# P_RAM_aux.net
KiCad netlist of a schematic drawn in Altium Designer
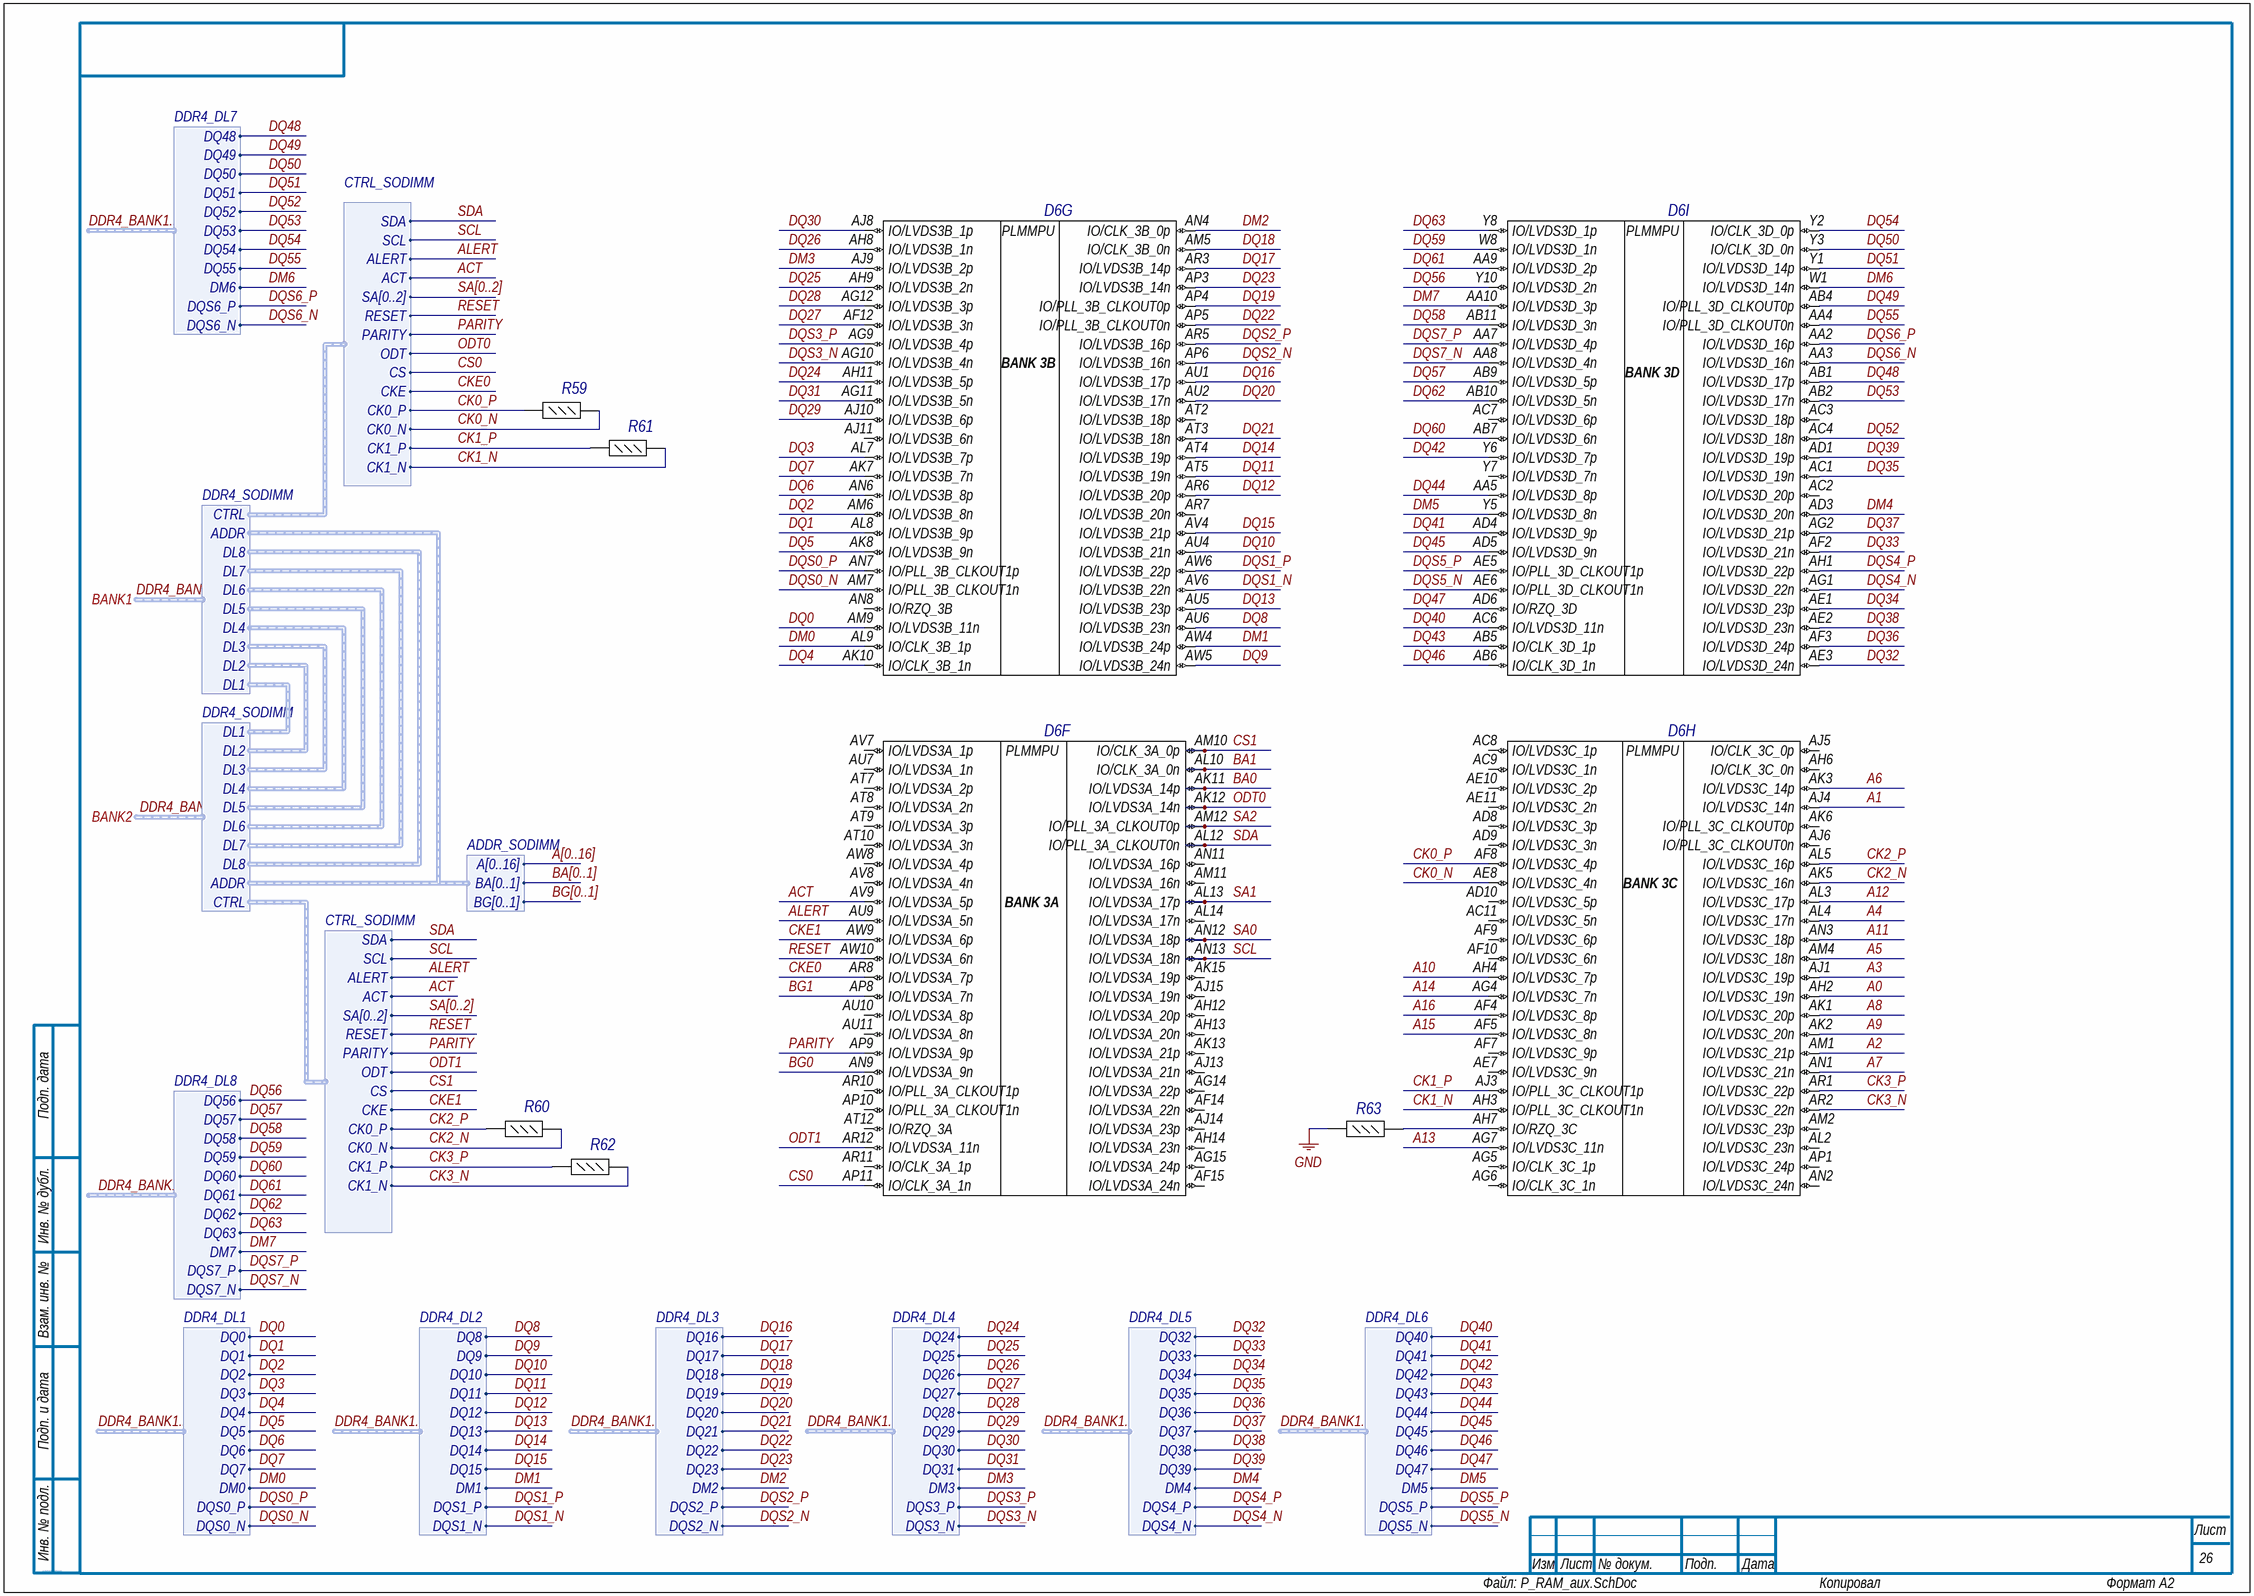
[diagram p0: P_RAM_aux.SchDoc]

(export (version "E")
  (design (tool "Eeschema 10.0.6"))
  (components
    (comp (ref "D6")
      (value "10AS066N3F40E2SGE2")
      (footprint "ALTR-FBGA1517_A-350")
      (libsource (lib "MiniPC DB") (part "10AS066N3F40"))
    )
    (comp (ref "R59")
      (value "RC0402JR-0739RL")
      (footprint "RESC1005X40X25LL05T05")
      (description "Chip Resistor, 39 Ohm, +/- 5%, 0.063 W, -55 to 155 degC, 0402 (1005 Metric), RoHS, Tape and Reel")
      (fields (field (name "TOLERANCE") "5%"))
      (libsource (lib "MiniPC DB") (part "RES-0.05"))
    )
    (comp (ref "R60")
      (value "RC0402JR-0739RL")
      (footprint "RESC1005X40X25LL05T05")
      (description "Chip Resistor, 39 Ohm, +/- 5%, 0.063 W, -55 to 155 degC, 0402 (1005 Metric), RoHS, Tape and Reel")
      (fields (field (name "TOLERANCE") "5%"))
      (libsource (lib "MiniPC DB") (part "RES-0.05"))
    )
    (comp (ref "R61")
      (value "RC0402JR-0739RL")
      (footprint "RESC1005X40X25LL05T05")
      (description "Chip Resistor, 39 Ohm, +/- 5%, 0.063 W, -55 to 155 degC, 0402 (1005 Metric), RoHS, Tape and Reel")
      (fields (field (name "TOLERANCE") "5%"))
      (libsource (lib "MiniPC DB") (part "RES-0.05"))
    )
    (comp (ref "R62")
      (value "RC0402JR-0739RL")
      (footprint "RESC1005X40X25LL05T05")
      (description "Chip Resistor, 39 Ohm, +/- 5%, 0.063 W, -55 to 155 degC, 0402 (1005 Metric), RoHS, Tape and Reel")
      (fields (field (name "TOLERANCE") "5%"))
      (libsource (lib "MiniPC DB") (part "RES-0.05"))
    )
    (comp (ref "R63")
      (value "RC0402JR-0739RL")
      (footprint "RESC1005X40X25LL05T05")
      (description "Chip Resistor, 39 Ohm, +/- 5%, 0.063 W, -55 to 155 degC, 0402 (1005 Metric), RoHS, Tape and Reel")
      (fields (field (name "TOLERANCE") "5%"))
      (libsource (lib "MiniPC DB") (part "RES-0.05"))
    )
  )
  (nets
    (net (code "14") (name "/A0") (class "Default")
      (node (ref "D6") (pin "AH2") (pinfunction "IO/LVDS3C_19n_AH2") (pintype "bidirectional"))
    )
    (net (code "15") (name "/A1") (class "Default")
      (node (ref "D6") (pin "AJ4") (pinfunction "IO/LVDS3C_14n_AJ4") (pintype "bidirectional"))
    )
    (net (code "16") (name "/A2") (class "Default")
      (node (ref "D6") (pin "AM1") (pinfunction "IO/LVDS3C_21p_AM1") (pintype "bidirectional"))
    )
    (net (code "17") (name "/A3") (class "Default")
      (node (ref "D6") (pin "AJ1") (pinfunction "IO/LVDS3C_19p_AJ1") (pintype "bidirectional"))
    )
    (net (code "18") (name "/A4") (class "Default")
      (node (ref "D6") (pin "AL4") (pinfunction "IO/LVDS3C_17n_AL4") (pintype "bidirectional"))
    )
    (net (code "19") (name "/A5") (class "Default")
      (node (ref "D6") (pin "AM4") (pinfunction "IO/LVDS3C_18n_AM4") (pintype "bidirectional"))
    )
    (net (code "20") (name "/A6") (class "Default")
      (node (ref "D6") (pin "AK3") (pinfunction "IO/LVDS3C_14p_AK3") (pintype "bidirectional"))
    )
    (net (code "21") (name "/A7") (class "Default")
      (node (ref "D6") (pin "AN1") (pinfunction "IO/LVDS3C_21n_AN1") (pintype "bidirectional"))
    )
    (net (code "22") (name "/A8") (class "Default")
      (node (ref "D6") (pin "AK1") (pinfunction "IO/LVDS3C_20p_AK1") (pintype "bidirectional"))
    )
    (net (code "23") (name "/A9") (class "Default")
      (node (ref "D6") (pin "AK2") (pinfunction "IO/LVDS3C_20n_AK2") (pintype "bidirectional"))
    )
    (net (code "24") (name "/A10") (class "Default")
      (node (ref "D6") (pin "AH4") (pinfunction "IO/LVDS3C_7p_AH4") (pintype "bidirectional"))
    )
    (net (code "25") (name "/A11") (class "Default")
      (node (ref "D6") (pin "AN3") (pinfunction "IO/LVDS3C_18p_AN3") (pintype "bidirectional"))
    )
    (net (code "26") (name "/A12") (class "Default")
      (node (ref "D6") (pin "AL3") (pinfunction "IO/LVDS3C_17p_AL3") (pintype "bidirectional"))
    )
    (net (code "27") (name "/A13") (class "Default")
      (node (ref "D6") (pin "AG7") (pinfunction "IO/LVDS3C_11n_AG7") (pintype "bidirectional"))
    )
    (net (code "28") (name "/A14") (class "Default")
      (node (ref "D6") (pin "AG4") (pinfunction "IO/LVDS3C_7n_AG4") (pintype "bidirectional"))
    )
    (net (code "29") (name "/A15") (class "Default")
      (node (ref "D6") (pin "AF5") (pinfunction "IO/LVDS3C_8n_AF5") (pintype "bidirectional"))
    )
    (net (code "30") (name "/A16") (class "Default")
      (node (ref "D6") (pin "AF4") (pinfunction "IO/LVDS3C_8p_AF4") (pintype "bidirectional"))
    )
    (net (code "31") (name "/ACT") (class "Default")
      (node (ref "D6") (pin "AV9") (pinfunction "IO/LVDS3A_5p_AV9") (pintype "bidirectional"))
    )
    (net (code "32") (name "/ALERT") (class "Default")
      (node (ref "D6") (pin "AU9") (pinfunction "IO/LVDS3A_5n_AU9") (pintype "bidirectional"))
    )
    (net (code "34") (name "/BA0") (class "Default")
      (node (ref "D6") (pin "AK11") (pinfunction "IO/LVDS3A_14p_AK11") (pintype "bidirectional"))
    )
    (net (code "35") (name "/BA1") (class "Default")
      (node (ref "D6") (pin "AL10") (pinfunction "IO/CLK_3A_0n_AL10") (pintype "bidirectional"))
    )
    (net (code "37") (name "/BG0") (class "Default")
      (node (ref "D6") (pin "AN9") (pinfunction "IO/LVDS3A_9n_AN9") (pintype "bidirectional"))
    )
    (net (code "38") (name "/BG1") (class "Default")
      (node (ref "D6") (pin "AP8") (pinfunction "IO/LVDS3A_7n_AP8") (pintype "bidirectional"))
    )
    (net (code "40") (name "/CK0_N") (class "Default")
      (node (ref "D6") (pin "AE8") (pinfunction "IO/LVDS3C_4n_AE8") (pintype "bidirectional"))
      (node (ref "R59") (pin "2") (pinfunction "2_2") (pintype "passive"))
    )
    (net (code "41") (name "/CK0_P") (class "Default")
      (node (ref "D6") (pin "AF8") (pinfunction "IO/LVDS3C_4p_AF8") (pintype "bidirectional"))
      (node (ref "R59") (pin "1") (pinfunction "1_1") (pintype "passive"))
    )
    (net (code "42") (name "/CK1_N") (class "Default")
      (node (ref "D6") (pin "AH3") (pinfunction "IO/PLL_3C_CLKOUT1n_AH3") (pintype "bidirectional"))
      (node (ref "R61") (pin "2") (pinfunction "2_2") (pintype "passive"))
    )
    (net (code "43") (name "/CK1_P") (class "Default")
      (node (ref "D6") (pin "AJ3") (pinfunction "IO/PLL_3C_CLKOUT1p_AJ3") (pintype "bidirectional"))
      (node (ref "R61") (pin "1") (pinfunction "1_1") (pintype "passive"))
    )
    (net (code "44") (name "/CK2_N") (class "Default")
      (node (ref "D6") (pin "AK5") (pinfunction "IO/LVDS3C_16n_AK5") (pintype "bidirectional"))
      (node (ref "R60") (pin "2") (pinfunction "2_2") (pintype "passive"))
    )
    (net (code "45") (name "/CK2_P") (class "Default")
      (node (ref "D6") (pin "AL5") (pinfunction "IO/LVDS3C_16p_AL5") (pintype "bidirectional"))
      (node (ref "R60") (pin "1") (pinfunction "1_1") (pintype "passive"))
    )
    (net (code "46") (name "/CK3_N") (class "Default")
      (node (ref "D6") (pin "AR2") (pinfunction "IO/LVDS3C_22n_AR2") (pintype "bidirectional"))
      (node (ref "R62") (pin "2") (pinfunction "2_2") (pintype "passive"))
    )
    (net (code "47") (name "/CK3_P") (class "Default")
      (node (ref "D6") (pin "AR1") (pinfunction "IO/LVDS3C_22p_AR1") (pintype "bidirectional"))
      (node (ref "R62") (pin "1") (pinfunction "1_1") (pintype "passive"))
    )
    (net (code "48") (name "/CKE0") (class "Default")
      (node (ref "D6") (pin "AR8") (pinfunction "IO/LVDS3A_7p_AR8") (pintype "bidirectional"))
    )
    (net (code "49") (name "/CKE1") (class "Default")
      (node (ref "D6") (pin "AW9") (pinfunction "IO/LVDS3A_6p_AW9") (pintype "bidirectional"))
    )
    (net (code "50") (name "/CS0") (class "Default")
      (node (ref "D6") (pin "AP11") (pinfunction "IO/CLK_3A_1n_AP11") (pintype "bidirectional"))
    )
    (net (code "51") (name "/CS1") (class "Default")
      (node (ref "D6") (pin "AM10") (pinfunction "IO/CLK_3A_0p_AM10") (pintype "bidirectional"))
    )
    (net (code "60") (name "/DM0") (class "Default")
      (node (ref "D6") (pin "AL9") (pinfunction "IO/CLK_3B_1p_AL9") (pintype "bidirectional"))
    )
    (net (code "61") (name "/DM1") (class "Default")
      (node (ref "D6") (pin "AW4") (pinfunction "IO/LVDS3B_24p_AW4") (pintype "bidirectional"))
    )
    (net (code "62") (name "/DM2") (class "Default")
      (node (ref "D6") (pin "AN4") (pinfunction "IO/CLK_3B_0p_AN4") (pintype "bidirectional"))
    )
    (net (code "63") (name "/DM3") (class "Default")
      (node (ref "D6") (pin "AJ9") (pinfunction "IO/LVDS3B_2p_AJ9") (pintype "bidirectional"))
    )
    (net (code "64") (name "/DM4") (class "Default")
      (node (ref "D6") (pin "AD3") (pinfunction "IO/LVDS3D_20n_AD3") (pintype "bidirectional"))
    )
    (net (code "65") (name "/DM5") (class "Default")
      (node (ref "D6") (pin "Y5") (pinfunction "IO/LVDS3D_8n_Y5") (pintype "bidirectional"))
    )
    (net (code "66") (name "/DM6") (class "Default")
      (node (ref "D6") (pin "W1") (pinfunction "IO/LVDS3D_14n_W1") (pintype "bidirectional"))
    )
    (net (code "67") (name "/DM7") (class "Default")
      (node (ref "D6") (pin "AA10") (pinfunction "IO/LVDS3D_3p_AA10") (pintype "bidirectional"))
    )
    (net (code "68") (name "/DQ0") (class "Default")
      (node (ref "D6") (pin "AM9") (pinfunction "IO/LVDS3B_11n_AM9") (pintype "bidirectional"))
    )
    (net (code "69") (name "/DQ1") (class "Default")
      (node (ref "D6") (pin "AL8") (pinfunction "IO/LVDS3B_9p_AL8") (pintype "bidirectional"))
    )
    (net (code "70") (name "/DQ2") (class "Default")
      (node (ref "D6") (pin "AM6") (pinfunction "IO/LVDS3B_8n_AM6") (pintype "bidirectional"))
    )
    (net (code "71") (name "/DQ3") (class "Default")
      (node (ref "D6") (pin "AL7") (pinfunction "IO/LVDS3B_7p_AL7") (pintype "bidirectional"))
    )
    (net (code "72") (name "/DQ4") (class "Default")
      (node (ref "D6") (pin "AK10") (pinfunction "IO/CLK_3B_1n_AK10") (pintype "bidirectional"))
    )
    (net (code "73") (name "/DQ5") (class "Default")
      (node (ref "D6") (pin "AK8") (pinfunction "IO/LVDS3B_9n_AK8") (pintype "bidirectional"))
    )
    (net (code "74") (name "/DQ6") (class "Default")
      (node (ref "D6") (pin "AN6") (pinfunction "IO/LVDS3B_8p_AN6") (pintype "bidirectional"))
    )
    (net (code "75") (name "/DQ7") (class "Default")
      (node (ref "D6") (pin "AK7") (pinfunction "IO/LVDS3B_7n_AK7") (pintype "bidirectional"))
    )
    (net (code "76") (name "/DQ8") (class "Default")
      (node (ref "D6") (pin "AU6") (pinfunction "IO/LVDS3B_23n_AU6") (pintype "bidirectional"))
    )
    (net (code "77") (name "/DQ9") (class "Default")
      (node (ref "D6") (pin "AW5") (pinfunction "IO/LVDS3B_24n_AW5") (pintype "bidirectional"))
    )
    (net (code "78") (name "/DQ10") (class "Default")
      (node (ref "D6") (pin "AU4") (pinfunction "IO/LVDS3B_21n_AU4") (pintype "bidirectional"))
    )
    (net (code "79") (name "/DQ11") (class "Default")
      (node (ref "D6") (pin "AT5") (pinfunction "IO/LVDS3B_19n_AT5") (pintype "bidirectional"))
    )
    (net (code "80") (name "/DQ12") (class "Default")
      (node (ref "D6") (pin "AR6") (pinfunction "IO/LVDS3B_20p_AR6") (pintype "bidirectional"))
    )
    (net (code "81") (name "/DQ13") (class "Default")
      (node (ref "D6") (pin "AU5") (pinfunction "IO/LVDS3B_23p_AU5") (pintype "bidirectional"))
    )
    (net (code "82") (name "/DQ14") (class "Default")
      (node (ref "D6") (pin "AT4") (pinfunction "IO/LVDS3B_19p_AT4") (pintype "bidirectional"))
    )
    (net (code "83") (name "/DQ15") (class "Default")
      (node (ref "D6") (pin "AV4") (pinfunction "IO/LVDS3B_21p_AV4") (pintype "bidirectional"))
    )
    (net (code "84") (name "/DQ16") (class "Default")
      (node (ref "D6") (pin "AU1") (pinfunction "IO/LVDS3B_17p_AU1") (pintype "bidirectional"))
    )
    (net (code "85") (name "/DQ17") (class "Default")
      (node (ref "D6") (pin "AR3") (pinfunction "IO/LVDS3B_14p_AR3") (pintype "bidirectional"))
    )
    (net (code "86") (name "/DQ18") (class "Default")
      (node (ref "D6") (pin "AM5") (pinfunction "IO/CLK_3B_0n_AM5") (pintype "bidirectional"))
    )
    (net (code "87") (name "/DQ19") (class "Default")
      (node (ref "D6") (pin "AP4") (pinfunction "IO/PLL_3B_CLKOUT0p_AP4") (pintype "bidirectional"))
    )
    (net (code "88") (name "/DQ20") (class "Default")
      (node (ref "D6") (pin "AU2") (pinfunction "IO/LVDS3B_17n_AU2") (pintype "bidirectional"))
    )
    (net (code "89") (name "/DQ21") (class "Default")
      (node (ref "D6") (pin "AT3") (pinfunction "IO/LVDS3B_18n_AT3") (pintype "bidirectional"))
    )
    (net (code "90") (name "/DQ22") (class "Default")
      (node (ref "D6") (pin "AP5") (pinfunction "IO/PLL_3B_CLKOUT0n_AP5") (pintype "bidirectional"))
    )
    (net (code "91") (name "/DQ23") (class "Default")
      (node (ref "D6") (pin "AP3") (pinfunction "IO/LVDS3B_14n_AP3") (pintype "bidirectional"))
    )
    (net (code "92") (name "/DQ24") (class "Default")
      (node (ref "D6") (pin "AH11") (pinfunction "IO/LVDS3B_5p_AH11") (pintype "bidirectional"))
    )
    (net (code "93") (name "/DQ25") (class "Default")
      (node (ref "D6") (pin "AH9") (pinfunction "IO/LVDS3B_2n_AH9") (pintype "bidirectional"))
    )
    (net (code "94") (name "/DQ26") (class "Default")
      (node (ref "D6") (pin "AH8") (pinfunction "IO/LVDS3B_1n_AH8") (pintype "bidirectional"))
    )
    (net (code "95") (name "/DQ27") (class "Default")
      (node (ref "D6") (pin "AF12") (pinfunction "IO/LVDS3B_3n_AF12") (pintype "bidirectional"))
    )
    (net (code "96") (name "/DQ28") (class "Default")
      (node (ref "D6") (pin "AG12") (pinfunction "IO/LVDS3B_3p_AG12") (pintype "bidirectional"))
    )
    (net (code "97") (name "/DQ29") (class "Default")
      (node (ref "D6") (pin "AJ10") (pinfunction "IO/LVDS3B_6p_AJ10") (pintype "bidirectional"))
    )
    (net (code "98") (name "/DQ30") (class "Default")
      (node (ref "D6") (pin "AJ8") (pinfunction "IO/LVDS3B_1p_AJ8") (pintype "bidirectional"))
    )
    (net (code "99") (name "/DQ31") (class "Default")
      (node (ref "D6") (pin "AG11") (pinfunction "IO/LVDS3B_5n_AG11") (pintype "bidirectional"))
    )
    (net (code "100") (name "/DQ32") (class "Default")
      (node (ref "D6") (pin "AE3") (pinfunction "IO/LVDS3D_24n_AE3") (pintype "bidirectional"))
    )
    (net (code "101") (name "/DQ33") (class "Default")
      (node (ref "D6") (pin "AF2") (pinfunction "IO/LVDS3D_21n_AF2") (pintype "bidirectional"))
    )
    (net (code "102") (name "/DQ34") (class "Default")
      (node (ref "D6") (pin "AE1") (pinfunction "IO/LVDS3D_23p_AE1") (pintype "bidirectional"))
    )
    (net (code "103") (name "/DQ35") (class "Default")
      (node (ref "D6") (pin "AC1") (pinfunction "IO/LVDS3D_19n_AC1") (pintype "bidirectional"))
    )
    (net (code "104") (name "/DQ36") (class "Default")
      (node (ref "D6") (pin "AF3") (pinfunction "IO/LVDS3D_24p_AF3") (pintype "bidirectional"))
    )
    (net (code "105") (name "/DQ37") (class "Default")
      (node (ref "D6") (pin "AG2") (pinfunction "IO/LVDS3D_21p_AG2") (pintype "bidirectional"))
    )
    (net (code "106") (name "/DQ38") (class "Default")
      (node (ref "D6") (pin "AE2") (pinfunction "IO/LVDS3D_23n_AE2") (pintype "bidirectional"))
    )
    (net (code "107") (name "/DQ39") (class "Default")
      (node (ref "D6") (pin "AD1") (pinfunction "IO/LVDS3D_19p_AD1") (pintype "bidirectional"))
    )
    (net (code "108") (name "/DQ40") (class "Default")
      (node (ref "D6") (pin "AC6") (pinfunction "IO/LVDS3D_11n_AC6") (pintype "bidirectional"))
    )
    (net (code "109") (name "/DQ41") (class "Default")
      (node (ref "D6") (pin "AD4") (pinfunction "IO/LVDS3D_9p_AD4") (pintype "bidirectional"))
    )
    (net (code "110") (name "/DQ42") (class "Default")
      (node (ref "D6") (pin "Y6") (pinfunction "IO/LVDS3D_7p_Y6") (pintype "bidirectional"))
    )
    (net (code "111") (name "/DQ43") (class "Default")
      (node (ref "D6") (pin "AB5") (pinfunction "IO/CLK_3D_1p_AB5") (pintype "bidirectional"))
    )
    (net (code "112") (name "/DQ44") (class "Default")
      (node (ref "D6") (pin "AA5") (pinfunction "IO/LVDS3D_8p_AA5") (pintype "bidirectional"))
    )
    (net (code "113") (name "/DQ45") (class "Default")
      (node (ref "D6") (pin "AD5") (pinfunction "IO/LVDS3D_9n_AD5") (pintype "bidirectional"))
    )
    (net (code "114") (name "/DQ46") (class "Default")
      (node (ref "D6") (pin "AB6") (pinfunction "IO/CLK_3D_1n_AB6") (pintype "bidirectional"))
    )
    (net (code "115") (name "/DQ47") (class "Default")
      (node (ref "D6") (pin "AD6") (pinfunction "IO/RZQ_3D_AD6") (pintype "bidirectional"))
    )
    (net (code "116") (name "/DQ48") (class "Default")
      (node (ref "D6") (pin "AB1") (pinfunction "IO/LVDS3D_17p_AB1") (pintype "bidirectional"))
    )
    (net (code "117") (name "/DQ49") (class "Default")
      (node (ref "D6") (pin "AB4") (pinfunction "IO/PLL_3D_CLKOUT0p_AB4") (pintype "bidirectional"))
    )
    (net (code "118") (name "/DQ50") (class "Default")
      (node (ref "D6") (pin "Y3") (pinfunction "IO/CLK_3D_0n_Y3") (pintype "bidirectional"))
    )
    (net (code "119") (name "/DQ51") (class "Default")
      (node (ref "D6") (pin "Y1") (pinfunction "IO/LVDS3D_14p_Y1") (pintype "bidirectional"))
    )
    (net (code "120") (name "/DQ52") (class "Default")
      (node (ref "D6") (pin "AC4") (pinfunction "IO/LVDS3D_18n_AC4") (pintype "bidirectional"))
    )
    (net (code "121") (name "/DQ53") (class "Default")
      (node (ref "D6") (pin "AB2") (pinfunction "IO/LVDS3D_17n_AB2") (pintype "bidirectional"))
    )
    (net (code "122") (name "/DQ54") (class "Default")
      (node (ref "D6") (pin "Y2") (pinfunction "IO/CLK_3D_0p_Y2") (pintype "bidirectional"))
    )
    (net (code "123") (name "/DQ55") (class "Default")
      (node (ref "D6") (pin "AA4") (pinfunction "IO/PLL_3D_CLKOUT0n_AA4") (pintype "bidirectional"))
    )
    (net (code "124") (name "/DQ56") (class "Default")
      (node (ref "D6") (pin "Y10") (pinfunction "IO/LVDS3D_2n_Y10") (pintype "bidirectional"))
    )
    (net (code "125") (name "/DQ57") (class "Default")
      (node (ref "D6") (pin "AB9") (pinfunction "IO/LVDS3D_5p_AB9") (pintype "bidirectional"))
    )
    (net (code "126") (name "/DQ58") (class "Default")
      (node (ref "D6") (pin "AB11") (pinfunction "IO/LVDS3D_3n_AB11") (pintype "bidirectional"))
    )
    (net (code "127") (name "/DQ59") (class "Default")
      (node (ref "D6") (pin "W8") (pinfunction "IO/LVDS3D_1n_W8") (pintype "bidirectional"))
    )
    (net (code "128") (name "/DQ60") (class "Default")
      (node (ref "D6") (pin "AB7") (pinfunction "IO/LVDS3D_6n_AB7") (pintype "bidirectional"))
    )
    (net (code "129") (name "/DQ61") (class "Default")
      (node (ref "D6") (pin "AA9") (pinfunction "IO/LVDS3D_2p_AA9") (pintype "bidirectional"))
    )
    (net (code "130") (name "/DQ62") (class "Default")
      (node (ref "D6") (pin "AB10") (pinfunction "IO/LVDS3D_5n_AB10") (pintype "bidirectional"))
    )
    (net (code "131") (name "/DQ63") (class "Default")
      (node (ref "D6") (pin "Y8") (pinfunction "IO/LVDS3D_1p_Y8") (pintype "bidirectional"))
    )
    (net (code "132") (name "/DQS0_N") (class "Default")
      (node (ref "D6") (pin "AM7") (pinfunction "IO/PLL_3B_CLKOUT1n_AM7") (pintype "bidirectional"))
    )
    (net (code "133") (name "/DQS0_P") (class "Default")
      (node (ref "D6") (pin "AN7") (pinfunction "IO/PLL_3B_CLKOUT1p_AN7") (pintype "bidirectional"))
    )
    (net (code "134") (name "/DQS1_N") (class "Default")
      (node (ref "D6") (pin "AV6") (pinfunction "IO/LVDS3B_22n_AV6") (pintype "bidirectional"))
    )
    (net (code "135") (name "/DQS1_P") (class "Default")
      (node (ref "D6") (pin "AW6") (pinfunction "IO/LVDS3B_22p_AW6") (pintype "bidirectional"))
    )
    (net (code "136") (name "/DQS2_N") (class "Default")
      (node (ref "D6") (pin "AP6") (pinfunction "IO/LVDS3B_16n_AP6") (pintype "bidirectional"))
    )
    (net (code "137") (name "/DQS2_P") (class "Default")
      (node (ref "D6") (pin "AR5") (pinfunction "IO/LVDS3B_16p_AR5") (pintype "bidirectional"))
    )
    (net (code "138") (name "/DQS3_N") (class "Default")
      (node (ref "D6") (pin "AG10") (pinfunction "IO/LVDS3B_4n_AG10") (pintype "bidirectional"))
    )
    (net (code "139") (name "/DQS3_P") (class "Default")
      (node (ref "D6") (pin "AG9") (pinfunction "IO/LVDS3B_4p_AG9") (pintype "bidirectional"))
    )
    (net (code "140") (name "/DQS4_N") (class "Default")
      (node (ref "D6") (pin "AG1") (pinfunction "IO/LVDS3D_22n_AG1") (pintype "bidirectional"))
    )
    (net (code "141") (name "/DQS4_P") (class "Default")
      (node (ref "D6") (pin "AH1") (pinfunction "IO/LVDS3D_22p_AH1") (pintype "bidirectional"))
    )
    (net (code "142") (name "/DQS5_N") (class "Default")
      (node (ref "D6") (pin "AE6") (pinfunction "IO/PLL_3D_CLKOUT1n_AE6") (pintype "bidirectional"))
    )
    (net (code "143") (name "/DQS5_P") (class "Default")
      (node (ref "D6") (pin "AE5") (pinfunction "IO/PLL_3D_CLKOUT1p_AE5") (pintype "bidirectional"))
    )
    (net (code "144") (name "/DQS6_N") (class "Default")
      (node (ref "D6") (pin "AA3") (pinfunction "IO/LVDS3D_16n_AA3") (pintype "bidirectional"))
    )
    (net (code "145") (name "/DQS6_P") (class "Default")
      (node (ref "D6") (pin "AA2") (pinfunction "IO/LVDS3D_16p_AA2") (pintype "bidirectional"))
    )
    (net (code "146") (name "/DQS7_N") (class "Default")
      (node (ref "D6") (pin "AA8") (pinfunction "IO/LVDS3D_4n_AA8") (pintype "bidirectional"))
    )
    (net (code "147") (name "/DQS7_P") (class "Default")
      (node (ref "D6") (pin "AA7") (pinfunction "IO/LVDS3D_4p_AA7") (pintype "bidirectional"))
    )
    (net (code "148") (name "/ODT0") (class "Default")
      (node (ref "D6") (pin "AK12") (pinfunction "IO/LVDS3A_14n_AK12") (pintype "bidirectional"))
    )
    (net (code "149") (name "/ODT1") (class "Default")
      (node (ref "D6") (pin "AR12") (pinfunction "IO/LVDS3A_11n_AR12") (pintype "bidirectional"))
    )
    (net (code "150") (name "/PARITY") (class "Default")
      (node (ref "D6") (pin "AP9") (pinfunction "IO/LVDS3A_9p_AP9") (pintype "bidirectional"))
    )
    (net (code "151") (name "/RESET") (class "Default")
      (node (ref "D6") (pin "AW10") (pinfunction "IO/LVDS3A_6n_AW10") (pintype "bidirectional"))
    )
    (net (code "152") (name "/SA0") (class "Default")
      (node (ref "D6") (pin "AN12") (pinfunction "IO/LVDS3A_18p_AN12") (pintype "bidirectional"))
    )
    (net (code "153") (name "/SA1") (class "Default")
      (node (ref "D6") (pin "AL13") (pinfunction "IO/LVDS3A_17p_AL13") (pintype "bidirectional"))
    )
    (net (code "154") (name "/SA2") (class "Default")
      (node (ref "D6") (pin "AM12") (pinfunction "IO/PLL_3A_CLKOUT0p_AM12") (pintype "bidirectional"))
    )
    (net (code "156") (name "/SCL") (class "Default")
      (node (ref "D6") (pin "AN13") (pinfunction "IO/LVDS3A_18n_AN13") (pintype "bidirectional"))
    )
    (net (code "157") (name "/SDA") (class "Default")
      (node (ref "D6") (pin "AL12") (pinfunction "IO/PLL_3A_CLKOUT0n_AL12") (pintype "bidirectional"))
    )
    (net (code "164") (name "GND") (class "Default")
      (node (ref "R63") (pin "1") (pinfunction "1_1") (pintype "passive"))
    )
    (net (code "165") (name "Net-(D6H-IO{slash}RZQ_3C)") (class "Default")
      (node (ref "D6") (pin "AH7") (pinfunction "IO/RZQ_3C_AH7") (pintype "bidirectional"))
      (node (ref "R63") (pin "2") (pinfunction "2_2") (pintype "passive"))
    )
    (net (code "166") (name "unconnected-(D6F-IO{slash}CLK_3A_1p-PadAR11)") (class "Default")
      (node (ref "D6") (pin "AR11") (pinfunction "IO/CLK_3A_1p_AR11") (pintype "bidirectional"))
    )
    (net (code "167") (name "unconnected-(D6F-IO{slash}LVDS3A_1n-PadAU7)") (class "Default")
      (node (ref "D6") (pin "AU7") (pinfunction "IO/LVDS3A_1n_AU7") (pintype "bidirectional"))
    )
    (net (code "168") (name "unconnected-(D6F-IO{slash}LVDS3A_1p-PadAV7)") (class "Default")
      (node (ref "D6") (pin "AV7") (pinfunction "IO/LVDS3A_1p_AV7") (pintype "bidirectional"))
    )
    (net (code "169") (name "unconnected-(D6F-IO{slash}LVDS3A_2n-PadAT8)") (class "Default")
      (node (ref "D6") (pin "AT8") (pinfunction "IO/LVDS3A_2n_AT8") (pintype "bidirectional"))
    )
    (net (code "170") (name "unconnected-(D6F-IO{slash}LVDS3A_2p-PadAT7)") (class "Default")
      (node (ref "D6") (pin "AT7") (pinfunction "IO/LVDS3A_2p_AT7") (pintype "bidirectional"))
    )
    (net (code "171") (name "unconnected-(D6F-IO{slash}LVDS3A_3n-PadAT10)") (class "Default")
      (node (ref "D6") (pin "AT10") (pinfunction "IO/LVDS3A_3n_AT10") (pintype "bidirectional"))
    )
    (net (code "172") (name "unconnected-(D6F-IO{slash}LVDS3A_3p-PadAT9)") (class "Default")
      (node (ref "D6") (pin "AT9") (pinfunction "IO/LVDS3A_3p_AT9") (pintype "bidirectional"))
    )
    (net (code "173") (name "unconnected-(D6F-IO{slash}LVDS3A_4n-PadAV8)") (class "Default")
      (node (ref "D6") (pin "AV8") (pinfunction "IO/LVDS3A_4n_AV8") (pintype "bidirectional"))
    )
    (net (code "174") (name "unconnected-(D6F-IO{slash}LVDS3A_4p-PadAW8)") (class "Default")
      (node (ref "D6") (pin "AW8") (pinfunction "IO/LVDS3A_4p_AW8") (pintype "bidirectional"))
    )
    (net (code "175") (name "unconnected-(D6F-IO{slash}LVDS3A_8n-PadAU11)") (class "Default")
      (node (ref "D6") (pin "AU11") (pinfunction "IO/LVDS3A_8n_AU11") (pintype "bidirectional"))
    )
    (net (code "176") (name "unconnected-(D6F-IO{slash}LVDS3A_8p-PadAU10)") (class "Default")
      (node (ref "D6") (pin "AU10") (pinfunction "IO/LVDS3A_8p_AU10") (pintype "bidirectional"))
    )
    (net (code "177") (name "unconnected-(D6F-IO{slash}LVDS3A_16n-PadAM11)") (class "Default")
      (node (ref "D6") (pin "AM11") (pinfunction "IO/LVDS3A_16n_AM11") (pintype "bidirectional"))
    )
    (net (code "178") (name "unconnected-(D6F-IO{slash}LVDS3A_16p-PadAN11)") (class "Default")
      (node (ref "D6") (pin "AN11") (pinfunction "IO/LVDS3A_16p_AN11") (pintype "bidirectional"))
    )
    (net (code "179") (name "unconnected-(D6F-IO{slash}LVDS3A_17n-PadAL14)") (class "Default")
      (node (ref "D6") (pin "AL14") (pinfunction "IO/LVDS3A_17n_AL14") (pintype "bidirectional"))
    )
    (net (code "180") (name "unconnected-(D6F-IO{slash}LVDS3A_19n-PadAJ15)") (class "Default")
      (node (ref "D6") (pin "AJ15") (pinfunction "IO/LVDS3A_19n_AJ15") (pintype "bidirectional"))
    )
    (net (code "181") (name "unconnected-(D6F-IO{slash}LVDS3A_19p-PadAK15)") (class "Default")
      (node (ref "D6") (pin "AK15") (pinfunction "IO/LVDS3A_19p_AK15") (pintype "bidirectional"))
    )
    (net (code "182") (name "unconnected-(D6F-IO{slash}LVDS3A_20n-PadAH13)") (class "Default")
      (node (ref "D6") (pin "AH13") (pinfunction "IO/LVDS3A_20n_AH13") (pintype "bidirectional"))
    )
    (net (code "183") (name "unconnected-(D6F-IO{slash}LVDS3A_20p-PadAH12)") (class "Default")
      (node (ref "D6") (pin "AH12") (pinfunction "IO/LVDS3A_20p_AH12") (pintype "bidirectional"))
    )
    (net (code "184") (name "unconnected-(D6F-IO{slash}LVDS3A_21n-PadAJ13)") (class "Default")
      (node (ref "D6") (pin "AJ13") (pinfunction "IO/LVDS3A_21n_AJ13") (pintype "bidirectional"))
    )
    (net (code "185") (name "unconnected-(D6F-IO{slash}LVDS3A_21p-PadAK13)") (class "Default")
      (node (ref "D6") (pin "AK13") (pinfunction "IO/LVDS3A_21p_AK13") (pintype "bidirectional"))
    )
    (net (code "186") (name "unconnected-(D6F-IO{slash}LVDS3A_22n-PadAF14)") (class "Default")
      (node (ref "D6") (pin "AF14") (pinfunction "IO/LVDS3A_22n_AF14") (pintype "bidirectional"))
    )
    (net (code "187") (name "unconnected-(D6F-IO{slash}LVDS3A_22p-PadAG14)") (class "Default")
      (node (ref "D6") (pin "AG14") (pinfunction "IO/LVDS3A_22p_AG14") (pintype "bidirectional"))
    )
    (net (code "188") (name "unconnected-(D6F-IO{slash}LVDS3A_23n-PadAH14)") (class "Default")
      (node (ref "D6") (pin "AH14") (pinfunction "IO/LVDS3A_23n_AH14") (pintype "bidirectional"))
    )
    (net (code "189") (name "unconnected-(D6F-IO{slash}LVDS3A_23p-PadAJ14)") (class "Default")
      (node (ref "D6") (pin "AJ14") (pinfunction "IO/LVDS3A_23p_AJ14") (pintype "bidirectional"))
    )
    (net (code "190") (name "unconnected-(D6F-IO{slash}LVDS3A_24n-PadAF15)") (class "Default")
      (node (ref "D6") (pin "AF15") (pinfunction "IO/LVDS3A_24n_AF15") (pintype "bidirectional"))
    )
    (net (code "191") (name "unconnected-(D6F-IO{slash}LVDS3A_24p-PadAG15)") (class "Default")
      (node (ref "D6") (pin "AG15") (pinfunction "IO/LVDS3A_24p_AG15") (pintype "bidirectional"))
    )
    (net (code "192") (name "unconnected-(D6F-IO{slash}PLL_3A_CLKOUT1n-PadAP10)") (class "Default")
      (node (ref "D6") (pin "AP10") (pinfunction "IO/PLL_3A_CLKOUT1n_AP10") (pintype "bidirectional"))
    )
    (net (code "193") (name "unconnected-(D6F-IO{slash}PLL_3A_CLKOUT1p-PadAR10)") (class "Default")
      (node (ref "D6") (pin "AR10") (pinfunction "IO/PLL_3A_CLKOUT1p_AR10") (pintype "bidirectional"))
    )
    (net (code "194") (name "unconnected-(D6F-IO{slash}RZQ_3A-PadAT12)") (class "Default")
      (node (ref "D6") (pin "AT12") (pinfunction "IO/RZQ_3A_AT12") (pintype "bidirectional"))
    )
    (net (code "195") (name "unconnected-(D6G-IO{slash}LVDS3B_6n-PadAJ11)") (class "Default")
      (node (ref "D6") (pin "AJ11") (pinfunction "IO/LVDS3B_6n_AJ11") (pintype "bidirectional"))
    )
    (net (code "196") (name "unconnected-(D6G-IO{slash}LVDS3B_18p-PadAT2)") (class "Default")
      (node (ref "D6") (pin "AT2") (pinfunction "IO/LVDS3B_18p_AT2") (pintype "bidirectional"))
    )
    (net (code "197") (name "unconnected-(D6G-IO{slash}LVDS3B_20n-PadAR7)") (class "Default")
      (node (ref "D6") (pin "AR7") (pinfunction "IO/LVDS3B_20n_AR7") (pintype "bidirectional"))
    )
    (net (code "198") (name "unconnected-(D6G-IO{slash}RZQ_3B-PadAN8)") (class "Default")
      (node (ref "D6") (pin "AN8") (pinfunction "IO/RZQ_3B_AN8") (pintype "bidirectional"))
    )
    (net (code "199") (name "unconnected-(D6H-IO{slash}CLK_3C_0n-PadAH6)") (class "Default")
      (node (ref "D6") (pin "AH6") (pinfunction "IO/CLK_3C_0n_AH6") (pintype "bidirectional"))
    )
    (net (code "200") (name "unconnected-(D6H-IO{slash}CLK_3C_0p-PadAJ5)") (class "Default")
      (node (ref "D6") (pin "AJ5") (pinfunction "IO/CLK_3C_0p_AJ5") (pintype "bidirectional"))
    )
    (net (code "201") (name "unconnected-(D6H-IO{slash}CLK_3C_1n-PadAG6)") (class "Default")
      (node (ref "D6") (pin "AG6") (pinfunction "IO/CLK_3C_1n_AG6") (pintype "bidirectional"))
    )
    (net (code "202") (name "unconnected-(D6H-IO{slash}CLK_3C_1p-PadAG5)") (class "Default")
      (node (ref "D6") (pin "AG5") (pinfunction "IO/CLK_3C_1p_AG5") (pintype "bidirectional"))
    )
    (net (code "203") (name "unconnected-(D6H-IO{slash}LVDS3C_1n-PadAC9)") (class "Default")
      (node (ref "D6") (pin "AC9") (pinfunction "IO/LVDS3C_1n_AC9") (pintype "bidirectional"))
    )
    (net (code "204") (name "unconnected-(D6H-IO{slash}LVDS3C_1p-PadAC8)") (class "Default")
      (node (ref "D6") (pin "AC8") (pinfunction "IO/LVDS3C_1p_AC8") (pintype "bidirectional"))
    )
    (net (code "205") (name "unconnected-(D6H-IO{slash}LVDS3C_2n-PadAE11)") (class "Default")
      (node (ref "D6") (pin "AE11") (pinfunction "IO/LVDS3C_2n_AE11") (pintype "bidirectional"))
    )
    (net (code "206") (name "unconnected-(D6H-IO{slash}LVDS3C_2p-PadAE10)") (class "Default")
      (node (ref "D6") (pin "AE10") (pinfunction "IO/LVDS3C_2p_AE10") (pintype "bidirectional"))
    )
    (net (code "207") (name "unconnected-(D6H-IO{slash}LVDS3C_3n-PadAD9)") (class "Default")
      (node (ref "D6") (pin "AD9") (pinfunction "IO/LVDS3C_3n_AD9") (pintype "bidirectional"))
    )
    (net (code "208") (name "unconnected-(D6H-IO{slash}LVDS3C_3p-PadAD8)") (class "Default")
      (node (ref "D6") (pin "AD8") (pinfunction "IO/LVDS3C_3p_AD8") (pintype "bidirectional"))
    )
    (net (code "209") (name "unconnected-(D6H-IO{slash}LVDS3C_5n-PadAC11)") (class "Default")
      (node (ref "D6") (pin "AC11") (pinfunction "IO/LVDS3C_5n_AC11") (pintype "bidirectional"))
    )
    (net (code "210") (name "unconnected-(D6H-IO{slash}LVDS3C_5p-PadAD10)") (class "Default")
      (node (ref "D6") (pin "AD10") (pinfunction "IO/LVDS3C_5p_AD10") (pintype "bidirectional"))
    )
    (net (code "211") (name "unconnected-(D6H-IO{slash}LVDS3C_6n-PadAF10)") (class "Default")
      (node (ref "D6") (pin "AF10") (pinfunction "IO/LVDS3C_6n_AF10") (pintype "bidirectional"))
    )
    (net (code "212") (name "unconnected-(D6H-IO{slash}LVDS3C_6p-PadAF9)") (class "Default")
      (node (ref "D6") (pin "AF9") (pinfunction "IO/LVDS3C_6p_AF9") (pintype "bidirectional"))
    )
    (net (code "213") (name "unconnected-(D6H-IO{slash}LVDS3C_9n-PadAE7)") (class "Default")
      (node (ref "D6") (pin "AE7") (pinfunction "IO/LVDS3C_9n_AE7") (pintype "bidirectional"))
    )
    (net (code "214") (name "unconnected-(D6H-IO{slash}LVDS3C_9p-PadAF7)") (class "Default")
      (node (ref "D6") (pin "AF7") (pinfunction "IO/LVDS3C_9p_AF7") (pintype "bidirectional"))
    )
    (net (code "215") (name "unconnected-(D6H-IO{slash}LVDS3C_23n-PadAL2)") (class "Default")
      (node (ref "D6") (pin "AL2") (pinfunction "IO/LVDS3C_23n_AL2") (pintype "bidirectional"))
    )
    (net (code "216") (name "unconnected-(D6H-IO{slash}LVDS3C_23p-PadAM2)") (class "Default")
      (node (ref "D6") (pin "AM2") (pinfunction "IO/LVDS3C_23p_AM2") (pintype "bidirectional"))
    )
    (net (code "217") (name "unconnected-(D6H-IO{slash}LVDS3C_24n-PadAN2)") (class "Default")
      (node (ref "D6") (pin "AN2") (pinfunction "IO/LVDS3C_24n_AN2") (pintype "bidirectional"))
    )
    (net (code "218") (name "unconnected-(D6H-IO{slash}LVDS3C_24p-PadAP1)") (class "Default")
      (node (ref "D6") (pin "AP1") (pinfunction "IO/LVDS3C_24p_AP1") (pintype "bidirectional"))
    )
    (net (code "219") (name "unconnected-(D6H-IO{slash}PLL_3C_CLKOUT0n-PadAJ6)") (class "Default")
      (node (ref "D6") (pin "AJ6") (pinfunction "IO/PLL_3C_CLKOUT0n_AJ6") (pintype "bidirectional"))
    )
    (net (code "220") (name "unconnected-(D6H-IO{slash}PLL_3C_CLKOUT0p-PadAK6)") (class "Default")
      (node (ref "D6") (pin "AK6") (pinfunction "IO/PLL_3C_CLKOUT0p_AK6") (pintype "bidirectional"))
    )
    (net (code "221") (name "unconnected-(D6I-IO{slash}LVDS3D_6p-PadAC7)") (class "Default")
      (node (ref "D6") (pin "AC7") (pinfunction "IO/LVDS3D_6p_AC7") (pintype "bidirectional"))
    )
    (net (code "222") (name "unconnected-(D6I-IO{slash}LVDS3D_7n-PadY7)") (class "Default")
      (node (ref "D6") (pin "Y7") (pinfunction "IO/LVDS3D_7n_Y7") (pintype "bidirectional"))
    )
    (net (code "223") (name "unconnected-(D6I-IO{slash}LVDS3D_18p-PadAC3)") (class "Default")
      (node (ref "D6") (pin "AC3") (pinfunction "IO/LVDS3D_18p_AC3") (pintype "bidirectional"))
    )
    (net (code "224") (name "unconnected-(D6I-IO{slash}LVDS3D_20p-PadAC2)") (class "Default")
      (node (ref "D6") (pin "AC2") (pinfunction "IO/LVDS3D_20p_AC2") (pintype "bidirectional"))
    )
  )
)
